# OpenKobold.net
KiCad netlist of a schematic drawn in EAGLE
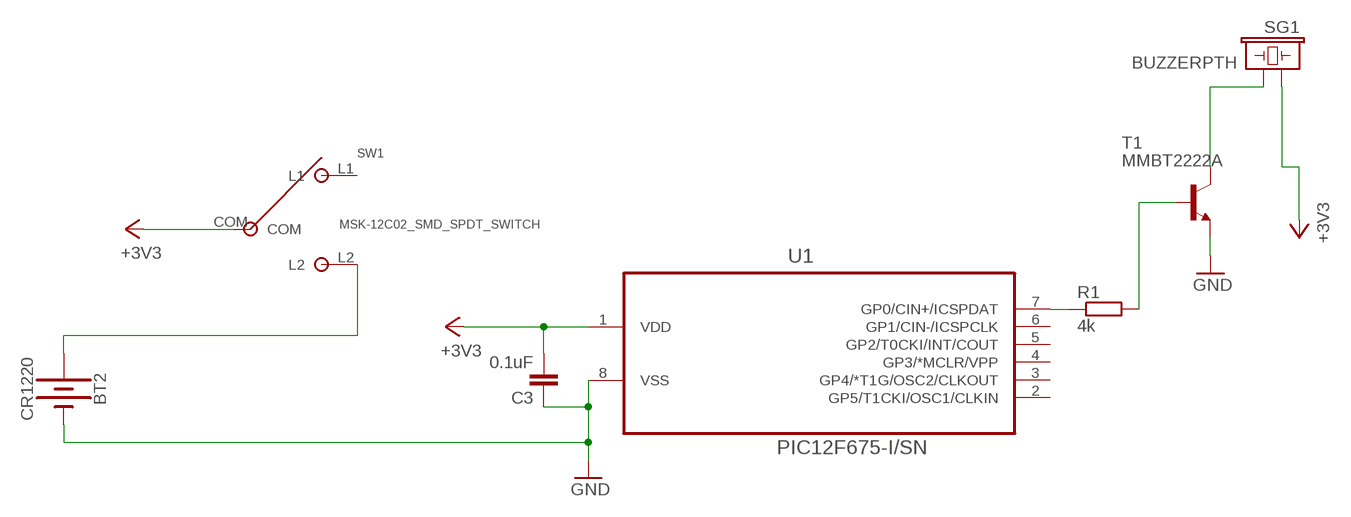
[diagram p0: schematic, sheet 1]

(export (version "E")
  (design (tool "Eeschema 10.0.6"))
  (components
    (comp (ref "BT2")
      (value "CR1220")
      (footprint "eagle-import:BATTCON_12MM")
      (libsource (lib "eagle-import") (part "BATTERY-12MM_SMD"))
    )
    (comp (ref "C3")
      (value "0.1uF")
      (footprint "eagle-import:C0805")
      (libsource (lib "eagle-import") (part "C-EUC0805"))
    )
    (comp (ref "R1")
      (value "4k")
      (footprint "eagle-import:R0805")
      (libsource (lib "eagle-import") (part "R-EU_R0805"))
    )
    (comp (ref "SG1")
      (value "BUZZERPTH")
      (footprint "eagle-import:BUZZER-12MM")
      (libsource (lib "eagle-import") (part "BUZZERPTH"))
    )
    (comp (ref "SW1")
      (value "MSK-12C02_SMD_SPDT_SWITCH")
      (footprint "eagle-import:MSK-12C02")
      (libsource (lib "eagle-import") (part "MSK-12C02_SMD_SPDT_SWITCH"))
    )
    (comp (ref "T1")
      (value "MMBT2222A")
      (footprint "eagle-import:SOT23-BEC")
      (libsource (lib "eagle-import") (part "-NPN-SOT23-BECMMBT2222ALT1"))
    )
    (comp (ref "U1")
      (value "PIC12F675-I/SN")
      (footprint "eagle-import:SOIC127P600X175-8N")
      (libsource (lib "eagle-import") (part "PIC12F675-I/SN"))
    )
  )
  (nets
    (net (code "1") (name "+3V3") (class "Default")
      (node (ref "C3") (pin "2") (pinfunction "2_2") (pintype "passive"))
      (node (ref "SG1") (pin "+") (pinfunction "1_+") (pintype "passive"))
      (node (ref "SW1") (pin "COM") (pinfunction "COM_COM") (pintype "bidirectional"))
      (node (ref "U1") (pin "1") (pinfunction "VDD_1") (pintype "power_in"))
    )
    (net (code "2") (name "GND") (class "Default")
      (node (ref "BT2") (pin "GND@1") (pinfunction "-_GND@1") (pintype "power_in"))
      (node (ref "C3") (pin "1") (pinfunction "1_1") (pintype "passive"))
      (node (ref "T1") (pin "E") (pinfunction "E_E") (pintype "passive"))
      (node (ref "U1") (pin "8") (pinfunction "VSS_8") (pintype "passive"))
    )
    (net (code "3") (name "Net-(BT2-+)") (class "Default")
      (node (ref "BT2") (pin "PWR@1") (pinfunction "+_PWR@1") (pintype "power_in"))
      (node (ref "SW1") (pin "L2") (pinfunction "L2_L2") (pintype "bidirectional"))
    )
    (net (code "4") (name "Net-(R1-Pad2)") (class "Default")
      (node (ref "R1") (pin "2") (pinfunction "2_2") (pintype "passive"))
      (node (ref "T1") (pin "B") (pinfunction "B_B") (pintype "passive"))
    )
    (net (code "5") (name "Net-(SG1-2)") (class "Default")
      (node (ref "SG1") (pin "-") (pinfunction "2_-") (pintype "passive"))
      (node (ref "T1") (pin "C") (pinfunction "C_C") (pintype "passive"))
    )
    (net (code "6") (name "Net-(U1-GP0{slash}CIN+{slash}ICSPDAT)") (class "Default")
      (node (ref "R1") (pin "1") (pinfunction "1_1") (pintype "passive"))
      (node (ref "U1") (pin "7") (pinfunction "GP0/CIN+/ICSPDAT_7") (pintype "bidirectional"))
    )
    (net (code "7") (name "unconnected-(SW1-PadL1)") (class "Default")
      (node (ref "SW1") (pin "L1") (pinfunction "L1_L1") (pintype "bidirectional"))
    )
    (net (code "8") (name "unconnected-(U1-GP1{slash}CIN-{slash}ICSPCLK-Pad6)") (class "Default")
      (node (ref "U1") (pin "6") (pinfunction "GP1/CIN-/ICSPCLK_6") (pintype "bidirectional"))
    )
    (net (code "9") (name "unconnected-(U1-GP2{slash}T0CKI{slash}INT{slash}COUT-Pad5)") (class "Default")
      (node (ref "U1") (pin "5") (pinfunction "GP2/T0CKI/INT/COUT_5") (pintype "bidirectional"))
    )
    (net (code "10") (name "unconnected-(U1-GP3{slash}*MCLR{slash}VPP-Pad4)") (class "Default")
      (node (ref "U1") (pin "4") (pinfunction "GP3/*MCLR/VPP_4") (pintype "bidirectional"))
    )
    (net (code "11") (name "unconnected-(U1-GP4{slash}*T1G{slash}OSC2{slash}CLKOUT-Pad3)") (class "Default")
      (node (ref "U1") (pin "3") (pinfunction "GP4/*T1G/OSC2/CLKOUT_3") (pintype "bidirectional"))
    )
    (net (code "12") (name "unconnected-(U1-GP5{slash}T1CKI{slash}OSC1{slash}CLKIN-Pad2)") (class "Default")
      (node (ref "U1") (pin "2") (pinfunction "GP5/T1CKI/OSC1/CLKIN_2") (pintype "bidirectional"))
    )
  )
)
